# EX-YU_64K_C64_CART.net
KiCad netlist of a schematic drawn in EAGLE
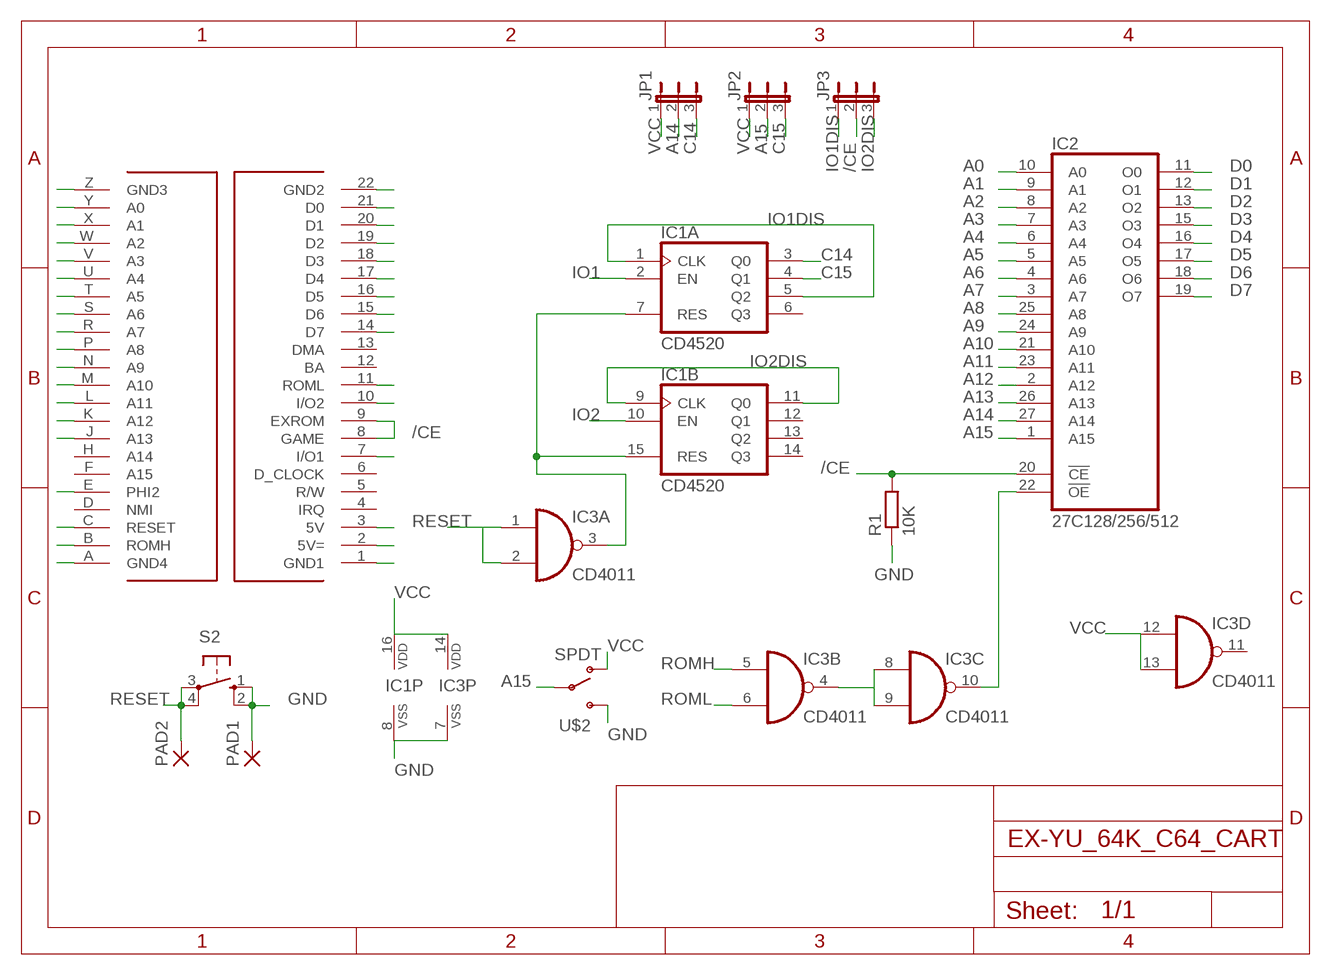
[diagram p0: schematic, sheet 1]

(export (version "E")
  (design (tool "Eeschema 10.0.6"))
  (components
    (comp (ref "IC1")
      (value "CD4520")
      (footprint "eagle-import:DIL16")
      (libsource (lib "eagle-import") (part "4520N"))
    )
    (comp (ref "IC2")
      (value "27C128/256/512")
      (footprint "eagle-import:DIL28")
      (libsource (lib "eagle-import") (part "27512"))
    )
    (comp (ref "IC3")
      (value "CD4011")
      (footprint "eagle-import:DIL14")
      (libsource (lib "eagle-import") (part "4011N"))
    )
    (comp (ref "JP1")
      (value "JP2E")
      (footprint "eagle-import:JP2")
      (libsource (lib "eagle-import") (part "JP2E"))
    )
    (comp (ref "JP2")
      (value "JP2E")
      (footprint "eagle-import:JP2")
      (libsource (lib "eagle-import") (part "JP2E"))
    )
    (comp (ref "JP3")
      (value "JP2E")
      (footprint "eagle-import:JP2")
      (libsource (lib "eagle-import") (part "JP2E"))
    )
    (comp (ref "PAD1")
      (value "SMD5")
      (footprint "eagle-import:SMD2,54-5,08")
      (libsource (lib "eagle-import") (part "SMD5"))
    )
    (comp (ref "PAD2")
      (value "SMD5")
      (footprint "eagle-import:SMD2,54-5,08")
      (libsource (lib "eagle-import") (part "SMD5"))
    )
    (comp (ref "R1")
      (value "10K")
      (footprint "eagle-import:0207_10")
      (libsource (lib "eagle-import") (part "R-EU_0207/10"))
    )
    (comp (ref "S2")
      (value "10-XX")
      (footprint "eagle-import:B3F-10XX")
      (fields (field (name "MPN") "B3F-1000"))
      (libsource (lib "eagle-import") (part "10-XX"))
    )
    (comp (ref "U$1")
      (value "C64_EXPANSION__CARTRIDGE")
      (footprint "eagle-import:C64_EXPANSION__CARTRIDGE")
      (libsource (lib "eagle-import") (part "C64_EXPANSION__CARTRIDGE"))
    )
    (comp (ref "U$2")
      (value "SPDT")
      (footprint "eagle-import:SPDT-SLIDE")
      (libsource (lib "eagle-import") (part "SPDT"))
    )
  )
  (nets
    (net (code "1") (name "/A0") (class "Default")
      (node (ref "IC2") (pin "10") (pinfunction "A0_10") (pintype "input"))
      (node (ref "U$1") (pin "Y") (pinfunction "A0_Y") (pintype "bidirectional"))
    )
    (net (code "2") (name "/A1") (class "Default")
      (node (ref "IC2") (pin "9") (pinfunction "A1_9") (pintype "input"))
      (node (ref "U$1") (pin "X") (pinfunction "A1_X") (pintype "bidirectional"))
    )
    (net (code "3") (name "/A2") (class "Default")
      (node (ref "IC2") (pin "8") (pinfunction "A2_8") (pintype "input"))
      (node (ref "U$1") (pin "W") (pinfunction "A2_W") (pintype "bidirectional"))
    )
    (net (code "4") (name "/A3") (class "Default")
      (node (ref "IC2") (pin "7") (pinfunction "A3_7") (pintype "input"))
      (node (ref "U$1") (pin "V") (pinfunction "A3_V") (pintype "bidirectional"))
    )
    (net (code "5") (name "/A4") (class "Default")
      (node (ref "IC2") (pin "6") (pinfunction "A4_6") (pintype "input"))
      (node (ref "U$1") (pin "U") (pinfunction "A4_U") (pintype "bidirectional"))
    )
    (net (code "6") (name "/A5") (class "Default")
      (node (ref "IC2") (pin "5") (pinfunction "A5_5") (pintype "input"))
      (node (ref "U$1") (pin "T") (pinfunction "A5_T") (pintype "bidirectional"))
    )
    (net (code "7") (name "/A6") (class "Default")
      (node (ref "IC2") (pin "4") (pinfunction "A6_4") (pintype "input"))
      (node (ref "U$1") (pin "S") (pinfunction "A6_S") (pintype "bidirectional"))
    )
    (net (code "8") (name "/A7") (class "Default")
      (node (ref "IC2") (pin "3") (pinfunction "A7_3") (pintype "input"))
      (node (ref "U$1") (pin "R") (pinfunction "A7_R") (pintype "bidirectional"))
    )
    (net (code "9") (name "/A8") (class "Default")
      (node (ref "IC2") (pin "25") (pinfunction "A8_25") (pintype "input"))
      (node (ref "U$1") (pin "P") (pinfunction "A8_P") (pintype "bidirectional"))
    )
    (net (code "10") (name "/A9") (class "Default")
      (node (ref "IC2") (pin "24") (pinfunction "A9_24") (pintype "input"))
      (node (ref "U$1") (pin "N") (pinfunction "A9_N") (pintype "bidirectional"))
    )
    (net (code "11") (name "/A10") (class "Default")
      (node (ref "IC2") (pin "21") (pinfunction "A10_21") (pintype "input"))
      (node (ref "U$1") (pin "M") (pinfunction "A10_M") (pintype "bidirectional"))
    )
    (net (code "12") (name "/A11") (class "Default")
      (node (ref "IC2") (pin "23") (pinfunction "A11_23") (pintype "input"))
      (node (ref "U$1") (pin "L") (pinfunction "A11_L") (pintype "bidirectional"))
    )
    (net (code "13") (name "/A12") (class "Default")
      (node (ref "IC2") (pin "2") (pinfunction "A12_2") (pintype "input"))
      (node (ref "U$1") (pin "K") (pinfunction "A12_K") (pintype "bidirectional"))
    )
    (net (code "14") (name "/A13") (class "Default")
      (node (ref "IC2") (pin "26") (pinfunction "A13_26") (pintype "input"))
      (node (ref "U$1") (pin "J") (pinfunction "A13_J") (pintype "bidirectional"))
    )
    (net (code "15") (name "/A14") (class "Default")
      (node (ref "IC2") (pin "27") (pinfunction "A14_27") (pintype "input"))
      (node (ref "JP1") (pin "2") (pinfunction "2_2") (pintype "passive"))
    )
    (net (code "16") (name "/A15") (class "Default")
      (node (ref "IC2") (pin "1") (pinfunction "A15_1") (pintype "input"))
      (node (ref "JP2") (pin "2") (pinfunction "2_2") (pintype "passive"))
      (node (ref "U$2") (pin "2") (pinfunction "2_2") (pintype "passive"))
    )
    (net (code "17") (name "/C14") (class "Default")
      (node (ref "IC1") (pin "3") (pinfunction "Q0_3") (pintype "output"))
      (node (ref "JP1") (pin "3") (pinfunction "3_3") (pintype "passive"))
    )
    (net (code "18") (name "/C15") (class "Default")
      (node (ref "IC1") (pin "4") (pinfunction "Q1_4") (pintype "output"))
      (node (ref "JP2") (pin "3") (pinfunction "3_3") (pintype "passive"))
    )
    (net (code "19") (name "/D0") (class "Default")
      (node (ref "IC2") (pin "11") (pinfunction "O0_11") (pintype "tri_state"))
      (node (ref "U$1") (pin "21") (pinfunction "D0_21") (pintype "bidirectional"))
    )
    (net (code "20") (name "/D1") (class "Default")
      (node (ref "IC2") (pin "12") (pinfunction "O1_12") (pintype "tri_state"))
      (node (ref "U$1") (pin "20") (pinfunction "D1_20") (pintype "bidirectional"))
    )
    (net (code "21") (name "/D2") (class "Default")
      (node (ref "IC2") (pin "13") (pinfunction "O2_13") (pintype "tri_state"))
      (node (ref "U$1") (pin "19") (pinfunction "D2_19") (pintype "bidirectional"))
    )
    (net (code "22") (name "/D3") (class "Default")
      (node (ref "IC2") (pin "15") (pinfunction "O3_15") (pintype "tri_state"))
      (node (ref "U$1") (pin "18") (pinfunction "D3_18") (pintype "bidirectional"))
    )
    (net (code "23") (name "/D4") (class "Default")
      (node (ref "IC2") (pin "16") (pinfunction "O4_16") (pintype "tri_state"))
      (node (ref "U$1") (pin "17") (pinfunction "D4_17") (pintype "bidirectional"))
    )
    (net (code "24") (name "/D5") (class "Default")
      (node (ref "IC2") (pin "17") (pinfunction "O5_17") (pintype "tri_state"))
      (node (ref "U$1") (pin "16") (pinfunction "D5_16") (pintype "bidirectional"))
    )
    (net (code "25") (name "/D6") (class "Default")
      (node (ref "IC2") (pin "18") (pinfunction "O6_18") (pintype "tri_state"))
      (node (ref "U$1") (pin "15") (pinfunction "D6_15") (pintype "bidirectional"))
    )
    (net (code "26") (name "/D7") (class "Default")
      (node (ref "IC2") (pin "19") (pinfunction "O7_19") (pintype "tri_state"))
      (node (ref "U$1") (pin "14") (pinfunction "D7_14") (pintype "bidirectional"))
    )
    (net (code "27") (name "/GND") (class "Default")
      (node (ref "IC1") (pin "8") (pinfunction "VSS_8") (pintype "power_in"))
      (node (ref "IC3") (pin "7") (pinfunction "VSS_7") (pintype "power_in"))
      (node (ref "PAD1") (pin "1") (pinfunction "P_1") (pintype "passive"))
      (node (ref "R1") (pin "1") (pinfunction "1_1") (pintype "passive"))
      (node (ref "S2") (pin "1") (pinfunction "S_1") (pintype "passive"))
      (node (ref "S2") (pin "2") (pinfunction "S1_2") (pintype "passive"))
      (node (ref "U$1") (pin "1") (pinfunction "GND1_1") (pintype "bidirectional"))
      (node (ref "U$1") (pin "22") (pinfunction "GND2_22") (pintype "bidirectional"))
      (node (ref "U$1") (pin "A") (pinfunction "GND4_A") (pintype "bidirectional"))
      (node (ref "U$1") (pin "Z") (pinfunction "GND3_Z") (pintype "bidirectional"))
      (node (ref "U$2") (pin "3") (pinfunction "3_3") (pintype "passive"))
    )
    (net (code "28") (name "/IO1") (class "Default")
      (node (ref "IC1") (pin "2") (pinfunction "EN_2") (pintype "input"))
      (node (ref "U$1") (pin "7") (pinfunction "I/O1_7") (pintype "bidirectional"))
    )
    (net (code "29") (name "/IO1DIS") (class "Default")
      (node (ref "IC1") (pin "1") (pinfunction "CLK_1") (pintype "input"))
      (node (ref "IC1") (pin "5") (pinfunction "Q2_5") (pintype "output"))
      (node (ref "JP3") (pin "1") (pinfunction "1_1") (pintype "passive"))
    )
    (net (code "30") (name "/IO2") (class "Default")
      (node (ref "IC1") (pin "10") (pinfunction "EN_10") (pintype "input"))
      (node (ref "U$1") (pin "10") (pinfunction "I/O2_10") (pintype "bidirectional"))
    )
    (net (code "31") (name "/IO2DIS") (class "Default")
      (node (ref "IC1") (pin "11") (pinfunction "Q0_11") (pintype "output"))
      (node (ref "IC1") (pin "9") (pinfunction "CLK_9") (pintype "input"))
      (node (ref "JP3") (pin "3") (pinfunction "3_3") (pintype "passive"))
    )
    (net (code "32") (name "/RESET") (class "Default")
      (node (ref "IC3") (pin "1") (pinfunction "I0_1") (pintype "input"))
      (node (ref "IC3") (pin "2") (pinfunction "I1_2") (pintype "input"))
      (node (ref "PAD2") (pin "1") (pinfunction "P_1") (pintype "passive"))
      (node (ref "S2") (pin "3") (pinfunction "P_3") (pintype "passive"))
      (node (ref "S2") (pin "4") (pinfunction "P1_4") (pintype "passive"))
      (node (ref "U$1") (pin "C") (pinfunction "RESET_C") (pintype "bidirectional"))
    )
    (net (code "33") (name "/ROMH") (class "Default")
      (node (ref "IC3") (pin "5") (pinfunction "I0_5") (pintype "input"))
      (node (ref "U$1") (pin "B") (pinfunction "ROMH_B") (pintype "bidirectional"))
    )
    (net (code "34") (name "/ROML") (class "Default")
      (node (ref "IC3") (pin "6") (pinfunction "I1_6") (pintype "input"))
      (node (ref "U$1") (pin "11") (pinfunction "ROML_11") (pintype "bidirectional"))
    )
    (net (code "35") (name "/VCC") (class "Default")
      (node (ref "IC1") (pin "16") (pinfunction "VDD_16") (pintype "power_in"))
      (node (ref "IC3") (pin "12") (pinfunction "I0_12") (pintype "input"))
      (node (ref "IC3") (pin "13") (pinfunction "I1_13") (pintype "input"))
      (node (ref "IC3") (pin "14") (pinfunction "VDD_14") (pintype "power_in"))
      (node (ref "JP1") (pin "1") (pinfunction "1_1") (pintype "passive"))
      (node (ref "JP2") (pin "1") (pinfunction "1_1") (pintype "passive"))
      (node (ref "U$1") (pin "2") (pinfunction "5V=_2") (pintype "bidirectional"))
      (node (ref "U$1") (pin "3") (pinfunction "5V_3") (pintype "bidirectional"))
      (node (ref "U$2") (pin "1") (pinfunction "1_1") (pintype "passive"))
    )
    (net (code "36") (name "/{slash}CE") (class "Default")
      (node (ref "IC2") (pin "20") (pinfunction "~{CE}_20") (pintype "input"))
      (node (ref "JP3") (pin "2") (pinfunction "2_2") (pintype "passive"))
      (node (ref "R1") (pin "2") (pinfunction "2_2") (pintype "passive"))
      (node (ref "U$1") (pin "8") (pinfunction "GAME_8") (pintype "bidirectional"))
      (node (ref "U$1") (pin "9") (pinfunction "EXROM_9") (pintype "bidirectional"))
    )
    (net (code "37") (name "Net-(IC1A-RES)") (class "Default")
      (node (ref "IC1") (pin "15") (pinfunction "RES_15") (pintype "input"))
      (node (ref "IC1") (pin "7") (pinfunction "RES_7") (pintype "input"))
      (node (ref "IC3") (pin "3") (pinfunction "O_3") (pintype "output"))
    )
    (net (code "38") (name "Net-(IC2A-~{OE})") (class "Default")
      (node (ref "IC2") (pin "22") (pinfunction "~{OE}_22") (pintype "input"))
      (node (ref "IC3") (pin "10") (pinfunction "O_10") (pintype "output"))
    )
    (net (code "39") (name "Net-(IC3B-O)") (class "Default")
      (node (ref "IC3") (pin "4") (pinfunction "O_4") (pintype "output"))
      (node (ref "IC3") (pin "8") (pinfunction "I0_8") (pintype "input"))
      (node (ref "IC3") (pin "9") (pinfunction "I1_9") (pintype "input"))
    )
    (net (code "40") (name "unconnected-(IC1A-Q3-Pad6)") (class "Default")
      (node (ref "IC1") (pin "6") (pinfunction "Q3_6") (pintype "output"))
    )
    (net (code "41") (name "unconnected-(IC1B-Q1-Pad12)") (class "Default")
      (node (ref "IC1") (pin "12") (pinfunction "Q1_12") (pintype "output"))
    )
    (net (code "42") (name "unconnected-(IC1B-Q2-Pad13)") (class "Default")
      (node (ref "IC1") (pin "13") (pinfunction "Q2_13") (pintype "output"))
    )
    (net (code "43") (name "unconnected-(IC1B-Q3-Pad14)") (class "Default")
      (node (ref "IC1") (pin "14") (pinfunction "Q3_14") (pintype "output"))
    )
    (net (code "44") (name "unconnected-(IC3D-O-Pad11)") (class "Default")
      (node (ref "IC3") (pin "11") (pinfunction "O_11") (pintype "output"))
    )
    (net (code "45") (name "unconnected-(U$1-A14-PadH)") (class "Default")
      (node (ref "U$1") (pin "H") (pinfunction "A14_H") (pintype "bidirectional"))
    )
    (net (code "46") (name "unconnected-(U$1-A15-PadF)") (class "Default")
      (node (ref "U$1") (pin "F") (pinfunction "A15_F") (pintype "bidirectional"))
    )
    (net (code "47") (name "unconnected-(U$1-BA-Pad12)") (class "Default")
      (node (ref "U$1") (pin "12") (pinfunction "BA_12") (pintype "bidirectional"))
    )
    (net (code "48") (name "unconnected-(U$1-DMA-Pad13)") (class "Default")
      (node (ref "U$1") (pin "13") (pinfunction "DMA_13") (pintype "bidirectional"))
    )
    (net (code "49") (name "unconnected-(U$1-D_CLOCK-Pad6)") (class "Default")
      (node (ref "U$1") (pin "6") (pinfunction "D_CLOCK_6") (pintype "bidirectional"))
    )
    (net (code "50") (name "unconnected-(U$1-IRQ-Pad4)") (class "Default")
      (node (ref "U$1") (pin "4") (pinfunction "IRQ_4") (pintype "bidirectional"))
    )
    (net (code "51") (name "unconnected-(U$1-NMI-PadD)") (class "Default")
      (node (ref "U$1") (pin "D") (pinfunction "NMI_D") (pintype "bidirectional"))
    )
    (net (code "52") (name "unconnected-(U$1-PHI2-PadE)") (class "Default")
      (node (ref "U$1") (pin "E") (pinfunction "PHI2_E") (pintype "bidirectional"))
    )
    (net (code "53") (name "unconnected-(U$1-R{slash}W-Pad5)") (class "Default")
      (node (ref "U$1") (pin "5") (pinfunction "R/W_5") (pintype "bidirectional"))
    )
  )
)
